# SCH_Iris_OnBoardSystem_Schematic.net
KiCad netlist of a schematic drawn in EasyEDA
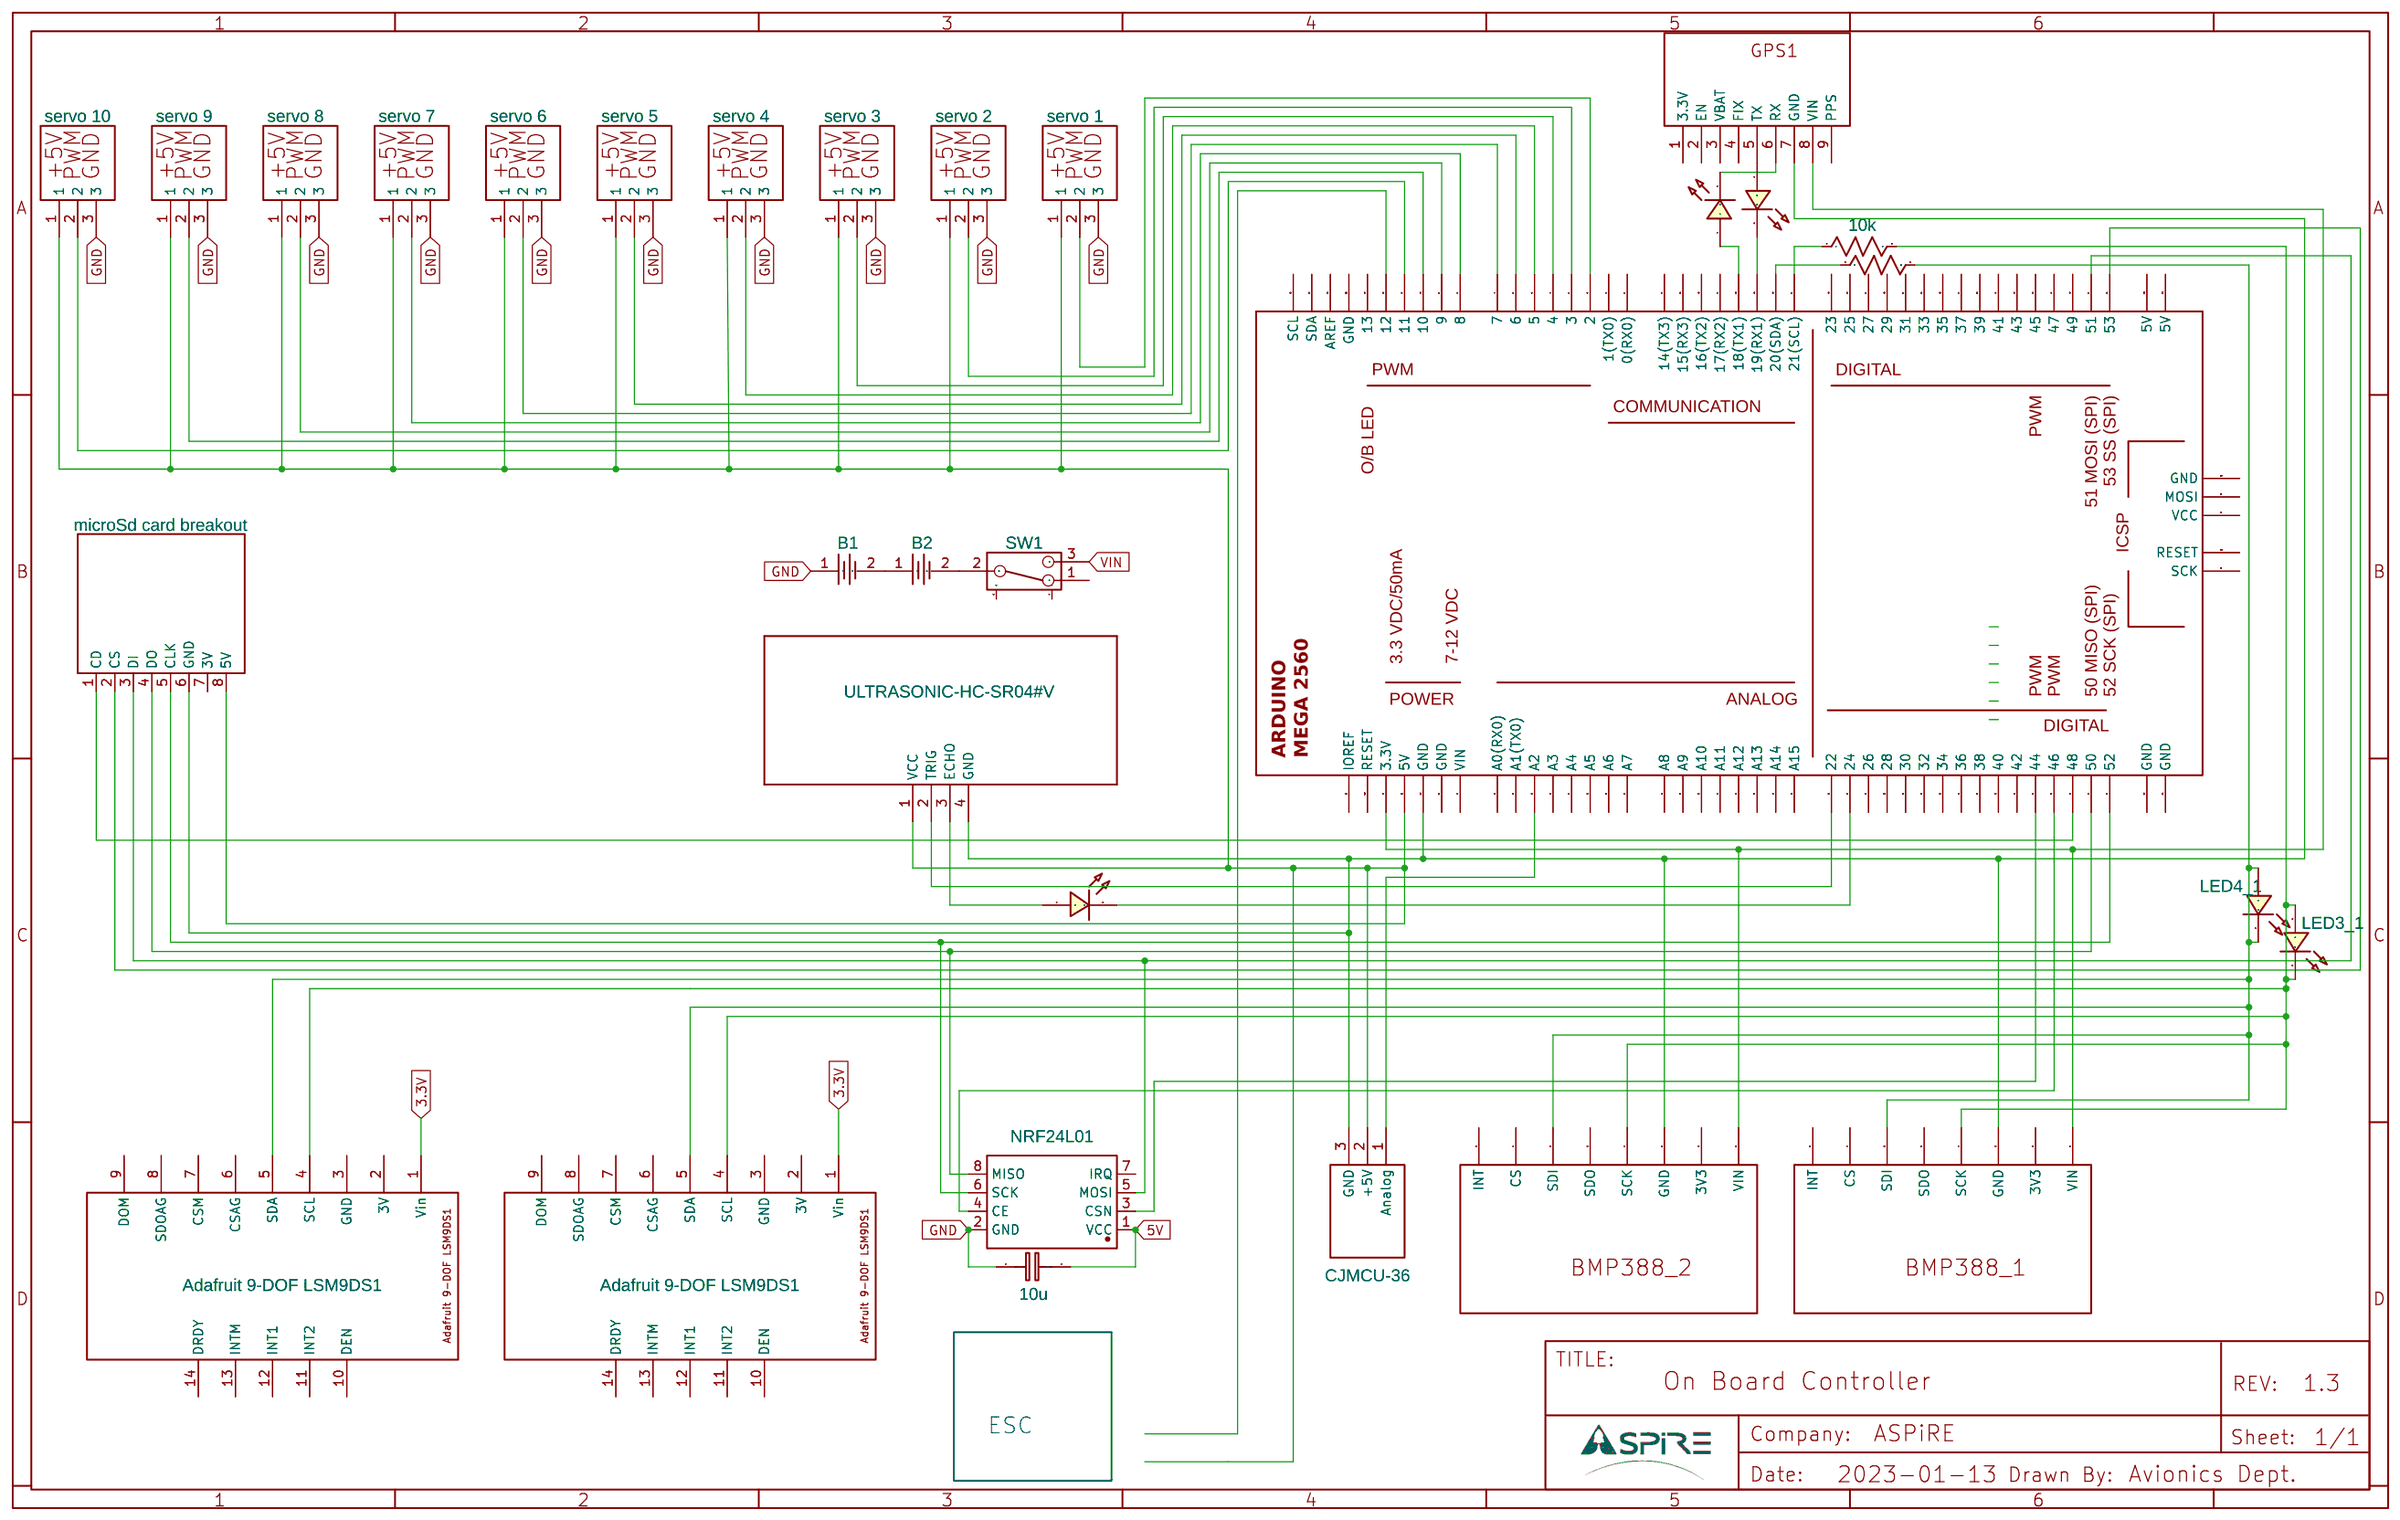
[diagram p0: schematic sheet]

(export (version "E")
  (design (tool "Eeschema 10.0.6"))
  (components
    (comp (ref "B1")
      (value "CR1220-2")
      (fields (field (name "BOM_Supplier Part") "C70381"))
      (libsource (lib "") (part "CR1220-2"))
    )
    (comp (ref "B2")
      (value "CR1220-2")
      (fields (field (name "BOM_Supplier Part") "C70381"))
      (libsource (lib "") (part "CR1220-2"))
    )
    (comp (ref "C1_1") (value "10u") (libsource (lib "") (part "C_RAD-0.1_EU")))
    (comp (ref "CD") (value "microSd card breakout") (libsource (lib "") (part "microSd card breakout")))
    (comp (ref "GPS1")
      (value "ULTIMATE GPS MODULE")
      (fields
        (field (name "BOM_Manufacturer Part") "Solid State Relays")
        (field (name "BOM_Supplier Part") "746")
      )
      (libsource (lib "") (part "ULTIMATE GPS MODULE"))
    )
    (comp (ref "LED1_1")
      (value "LED-TH-3mm_R")
      (fields
        (field (name "BOM_Manufacturer Part") "204-10SDRD/S530-A3-L")
        (field (name "BOM_Supplier Part") "C84774")
      )
      (libsource (lib "") (part "LED-TH-3mm_R_4"))
    )
    (comp (ref "LED2_1")
      (value "LED-TH-3mm_R")
      (fields
        (field (name "BOM_Manufacturer Part") "204-10SDRD/S530-A3-L")
        (field (name "BOM_Supplier Part") "C84774")
      )
      (libsource (lib "") (part "LED-TH-3mm_R_1"))
    )
    (comp (ref "LED3_1")
      (value "LED-TH-3mm_R")
      (fields
        (field (name "BOM_Manufacturer Part") "204-10SDRD/S530-A3-L")
        (field (name "BOM_Supplier Part") "C84774")
      )
      (libsource (lib "") (part "LED-TH-3mm_R_2"))
    )
    (comp (ref "LED4_1")
      (value "LED-TH-3mm_R")
      (fields
        (field (name "BOM_Manufacturer Part") "204-10SDRD/S530-A3-L")
        (field (name "BOM_Supplier Part") "C84774")
      )
      (libsource (lib "") (part "LED-TH-3mm_R"))
    )
    (comp (ref "LED5_1")
      (value "LED-TH-3mm_R")
      (fields
        (field (name "BOM_Manufacturer Part") "204-10SDRD/S530-A3-L")
        (field (name "BOM_Supplier Part") "C84774")
      )
      (libsource (lib "") (part "LED-TH-3mm_R_3"))
    )
    (comp (ref "MK1")
      (value "NRF24L01")
      (fields (field (name "BOM_Manufacturer Part") "NF-04") (field (name "BOM_Supplier Part") "C90751"))
      (libsource (lib "") (part "NRF24L01"))
    )
    (comp (ref "R1_1") (value "1k") (libsource (lib "") (part "R_AXIAL-0.4_US_1")))
    (comp (ref "R2_1") (value "10k") (libsource (lib "") (part "R_AXIAL-0.4_US")))
    (comp (ref "SW1")
      (value "SK-12D02-VG5")
      (fields (field (name "BOM_Supplier Part") "C136722"))
      (libsource (lib "") (part "SK-12D02-VG5"))
    )
    (comp (ref "U1")
      (value "Adafruit 9-DOF LSM9DS1")
      (fields (field (name "BOM_Manufacturer Part") "4634") (field (name "BOM_Supplier Part") "ADA4634"))
      (libsource (lib "") (part "Adafruit 9-DOF LSM9DS1"))
    )
    (comp (ref "U4")
      (value "ADAFRUIT_BMP388_1")
      (fields (field (name "BOM_Manufacturer Part") "BMP388") (field (name "BOM_Supplier Part") "3966"))
      (libsource (lib "") (part "ADAFRUIT BMP388 BOARD COPY_1"))
    )
    (comp (ref "U5")
      (value "ADAFRUIT_BMP388_2")
      (fields (field (name "BOM_Manufacturer Part") "BMP388") (field (name "BOM_Supplier Part") "3966"))
      (libsource (lib "") (part "ADAFRUIT BMP388 BOARD COPY"))
    )
    (comp (ref "U6") (value "Am") (libsource (lib "") (part "Am")))
    (comp (ref "U15")
      (value "Adafruit 9-DOF LSM9DS1")
      (fields (field (name "BOM_Manufacturer Part") "4634") (field (name "BOM_Supplier Part") "ADA4634"))
      (libsource (lib "") (part "Adafruit 9-DOF LSM9DS1"))
    )
    (comp (ref "U16") (value "CJMCU-36") (libsource (lib "") (part "CJMCU-36")))
    (comp (ref "U17") (value "ULTRASONIC-HC-SR04#V") (libsource (lib "") (part "ULTRASONIC-HC-SR04#V")))
    (comp (ref "U18") (value "servo 10") (libsource (lib "") (part "servo")))
    (comp (ref "U19") (value "servo 9") (libsource (lib "") (part "servo")))
    (comp (ref "U20") (value "servo 8") (libsource (lib "") (part "servo")))
    (comp (ref "U21") (value "servo 7") (libsource (lib "") (part "servo")))
    (comp (ref "U22") (value "servo 6") (libsource (lib "") (part "servo")))
    (comp (ref "U23") (value "servo 5") (libsource (lib "") (part "servo")))
    (comp (ref "U24") (value "servo 4") (libsource (lib "") (part "servo")))
    (comp (ref "U25") (value "servo 3") (libsource (lib "") (part "servo")))
    (comp (ref "U26") (value "servo 2") (libsource (lib "") (part "servo")))
    (comp (ref "U27") (value "servo 1") (libsource (lib "") (part "servo")))
  )
  (nets
    (net (code "1") (name "3.3V") (class "Default")
      (node (ref "U1") (pin "1") (pinfunction "Vin_1") (pintype "unspecified"))
      (node (ref "U15") (pin "1") (pinfunction "Vin_1") (pintype "unspecified"))
    )
    (net (code "2") (name "5V") (class "Default")
      (node (ref "C1_1") (pin "2") (pinfunction "2_2") (pintype "unspecified"))
      (node (ref "MK1") (pin "1") (pinfunction "VCC_1") (pintype "unspecified"))
    )
    (net (code "3") (name "GND") (class "Default")
      (node (ref "B1") (pin "1") (pinfunction "1_1") (pintype "input"))
      (node (ref "C1_1") (pin "1") (pinfunction "1_1") (pintype "unspecified"))
      (node (ref "MK1") (pin "2") (pinfunction "GND_2") (pintype "unspecified"))
      (node (ref "U18") (pin "3") (pinfunction "3_3") (pintype "unspecified"))
      (node (ref "U19") (pin "3") (pinfunction "3_3") (pintype "unspecified"))
      (node (ref "U20") (pin "3") (pinfunction "3_3") (pintype "unspecified"))
      (node (ref "U21") (pin "3") (pinfunction "3_3") (pintype "unspecified"))
      (node (ref "U22") (pin "3") (pinfunction "3_3") (pintype "unspecified"))
      (node (ref "U23") (pin "3") (pinfunction "3_3") (pintype "unspecified"))
      (node (ref "U24") (pin "3") (pinfunction "3_3") (pintype "unspecified"))
      (node (ref "U25") (pin "3") (pinfunction "3_3") (pintype "unspecified"))
      (node (ref "U26") (pin "3") (pinfunction "3_3") (pintype "unspecified"))
      (node (ref "U27") (pin "3") (pinfunction "3_3") (pintype "unspecified"))
    )
    (net (code "4") (name "Net-(B1-Pad2)") (class "Default")
      (node (ref "B1") (pin "2") (pinfunction "2_2") (pintype "input"))
      (node (ref "B2") (pin "1") (pinfunction "1_1") (pintype "input"))
    )
    (net (code "5") (name "Net-(B2-Pad2)") (class "Default")
      (node (ref "B2") (pin "2") (pinfunction "2_2") (pintype "input"))
      (node (ref "SW1") (pin "2") (pinfunction "2_2") (pintype "unspecified"))
    )
    (net (code "6") (name "Net-(CD-5V)") (class "Default")
      (node (ref "CD") (pin "8") (pinfunction "5V_8") (pintype "passive"))
      (node (ref "U16") (pin "2") (pinfunction "+5V_2") (pintype "unspecified"))
      (node (ref "U17") (pin "1") (pinfunction "VCC_1") (pintype "passive"))
      (node (ref "U18") (pin "1") (pinfunction "1_1") (pintype "unspecified"))
      (node (ref "U19") (pin "1") (pinfunction "1_1") (pintype "unspecified"))
      (node (ref "U20") (pin "1") (pinfunction "1_1") (pintype "unspecified"))
      (node (ref "U21") (pin "1") (pinfunction "1_1") (pintype "unspecified"))
      (node (ref "U22") (pin "1") (pinfunction "1_1") (pintype "unspecified"))
      (node (ref "U23") (pin "1") (pinfunction "1_1") (pintype "unspecified"))
      (node (ref "U24") (pin "1") (pinfunction "1_1") (pintype "unspecified"))
      (node (ref "U25") (pin "1") (pinfunction "1_1") (pintype "unspecified"))
      (node (ref "U26") (pin "1") (pinfunction "1_1") (pintype "unspecified"))
      (node (ref "U27") (pin "1") (pinfunction "1_1") (pintype "unspecified"))
      (node (ref "U6") (pin "5V@0") (pinfunction "5V_5V@0") (pintype "unspecified"))
    )
    (net (code "7") (name "Net-(CD-CD)") (class "Default")
      (node (ref "CD") (pin "1") (pinfunction "CD_1") (pintype "unspecified"))
      (node (ref "U6") (pin "48") (pinfunction "48_48") (pintype "unspecified"))
    )
    (net (code "8") (name "Net-(CD-CLK)") (class "Default")
      (node (ref "CD") (pin "5") (pinfunction "CLK_5") (pintype "input"))
      (node (ref "MK1") (pin "6") (pinfunction "SCK_6") (pintype "unspecified"))
      (node (ref "U6") (pin "52") (pinfunction "52_52") (pintype "unspecified"))
    )
    (net (code "9") (name "Net-(CD-CS)") (class "Default")
      (node (ref "CD") (pin "2") (pinfunction "CS_2") (pintype "input"))
      (node (ref "U6") (pin "53") (pinfunction "53_53") (pintype "unspecified"))
    )
    (net (code "10") (name "Net-(CD-DI)") (class "Default")
      (node (ref "CD") (pin "3") (pinfunction "DI_3") (pintype "bidirectional"))
      (node (ref "MK1") (pin "5") (pinfunction "MOSI_5") (pintype "unspecified"))
      (node (ref "U6") (pin "51") (pinfunction "51_51") (pintype "unspecified"))
    )
    (net (code "11") (name "Net-(CD-DO)") (class "Default")
      (node (ref "CD") (pin "4") (pinfunction "DO_4") (pintype "bidirectional"))
      (node (ref "MK1") (pin "8") (pinfunction "MISO_8") (pintype "unspecified"))
      (node (ref "U6") (pin "50") (pinfunction "50_50") (pintype "unspecified"))
    )
    (net (code "12") (name "Net-(CD-GND)") (class "Default")
      (node (ref "CD") (pin "6") (pinfunction "GND_6") (pintype "passive"))
      (node (ref "GPS1") (pin "7") (pinfunction "GND_7") (pintype "unspecified"))
      (node (ref "U16") (pin "3") (pinfunction "GND_3") (pintype "unspecified"))
      (node (ref "U17") (pin "4") (pinfunction "GND_4") (pintype "passive"))
      (node (ref "U4") (pin "3") (pinfunction "GND_3") (pintype "passive"))
      (node (ref "U5") (pin "3") (pinfunction "GND_3") (pintype "passive"))
      (node (ref "U6") (pin "GND@0") (pinfunction "GND_GND@0") (pintype "unspecified"))
    )
    (net (code "13") (name "Net-(GPS1-RX)") (class "Default")
      (node (ref "GPS1") (pin "6") (pinfunction "RX_6") (pintype "unspecified"))
      (node (ref "LED5_1") (pin "2") (pinfunction "2_2") (pintype "unspecified"))
    )
    (net (code "14") (name "Net-(GPS1-TX)") (class "Default")
      (node (ref "GPS1") (pin "5") (pinfunction "TX_5") (pintype "unspecified"))
      (node (ref "LED2_1") (pin "1") (pinfunction "1_1") (pintype "unspecified"))
    )
    (net (code "15") (name "Net-(GPS1-VIN)") (class "Default")
      (node (ref "GPS1") (pin "8") (pinfunction "VIN_8") (pintype "unspecified"))
      (node (ref "U4") (pin "1") (pinfunction "VIN_1") (pintype "passive"))
      (node (ref "U5") (pin "1") (pinfunction "VIN_1") (pintype "passive"))
      (node (ref "U6") (pin "3.3V") (pinfunction "3.3V_3.3V") (pintype "unspecified"))
    )
    (net (code "16") (name "Net-(LED1_1-Pad2)") (class "Default")
      (node (ref "LED1_1") (pin "2") (pinfunction "2_2") (pintype "unspecified"))
      (node (ref "U6") (pin "24") (pinfunction "24_24") (pintype "unspecified"))
    )
    (net (code "17") (name "Net-(MK1-CE)") (class "Default")
      (node (ref "MK1") (pin "4") (pinfunction "CE_4") (pintype "unspecified"))
      (node (ref "U6") (pin "46") (pinfunction "46_46") (pintype "unspecified"))
    )
    (net (code "18") (name "Net-(MK1-CSN)") (class "Default")
      (node (ref "MK1") (pin "3") (pinfunction "CSN_3") (pintype "unspecified"))
      (node (ref "U6") (pin "44") (pinfunction "44_44") (pintype "unspecified"))
    )
    (net (code "19") (name "Net-(U1-SCL)") (class "Default")
      (node (ref "LED3_1") (pin "1") (pinfunction "1_1") (pintype "unspecified"))
      (node (ref "LED3_1") (pin "2") (pinfunction "2_2") (pintype "unspecified"))
      (node (ref "R2_1") (pin "2") (pinfunction "2_2") (pintype "unspecified"))
      (node (ref "U1") (pin "4") (pinfunction "SCL_4") (pintype "unspecified"))
      (node (ref "U15") (pin "4") (pinfunction "SCL_4") (pintype "unspecified"))
      (node (ref "U4") (pin "4") (pinfunction "SCK_4") (pintype "input"))
      (node (ref "U5") (pin "4") (pinfunction "SCK_4") (pintype "input"))
    )
    (net (code "20") (name "Net-(U1-SDA)") (class "Default")
      (node (ref "LED4_1") (pin "1") (pinfunction "1_1") (pintype "unspecified"))
      (node (ref "LED4_1") (pin "2") (pinfunction "2_2") (pintype "unspecified"))
      (node (ref "R1_1") (pin "2") (pinfunction "2_2") (pintype "unspecified"))
      (node (ref "U1") (pin "5") (pinfunction "SDA_5") (pintype "unspecified"))
      (node (ref "U15") (pin "5") (pinfunction "SDA_5") (pintype "unspecified"))
      (node (ref "U4") (pin "6") (pinfunction "SDI_6") (pintype "bidirectional"))
      (node (ref "U5") (pin "6") (pinfunction "SDI_6") (pintype "bidirectional"))
    )
    (net (code "21") (name "Net-(U6-18(TX1))") (class "Default")
      (node (ref "LED5_1") (pin "1") (pinfunction "1_1") (pintype "unspecified"))
      (node (ref "U6") (pin "18") (pinfunction "18(TX1)_18") (pintype "unspecified"))
    )
    (net (code "22") (name "Net-(U6-19(RX1))") (class "Default")
      (node (ref "LED2_1") (pin "2") (pinfunction "2_2") (pintype "unspecified"))
      (node (ref "U6") (pin "19") (pinfunction "19(RX1)_19") (pintype "unspecified"))
    )
    (net (code "23") (name "Net-(U6-20(SDA))") (class "Default")
      (node (ref "R1_1") (pin "1") (pinfunction "1_1") (pintype "unspecified"))
      (node (ref "U6") (pin "20") (pinfunction "20(SDA)_20") (pintype "unspecified"))
    )
    (net (code "24") (name "Net-(U6-21(SCL))") (class "Default")
      (node (ref "R2_1") (pin "1") (pinfunction "1_1") (pintype "unspecified"))
      (node (ref "U6") (pin "21") (pinfunction "21(SCL)_21") (pintype "unspecified"))
    )
    (net (code "25") (name "Net-(U16-Analog)") (class "Default")
      (node (ref "U16") (pin "1") (pinfunction "Analog_1") (pintype "unspecified"))
      (node (ref "U6") (pin "A2") (pinfunction "A2_A2") (pintype "unspecified"))
    )
    (net (code "26") (name "Net-(U17-ECHO)") (class "Default")
      (node (ref "LED1_1") (pin "1") (pinfunction "1_1") (pintype "unspecified"))
      (node (ref "U17") (pin "3") (pinfunction "ECHO_3") (pintype "output"))
    )
    (net (code "27") (name "Net-(U17-TRIG)") (class "Default")
      (node (ref "U17") (pin "2") (pinfunction "TRIG_2") (pintype "input"))
      (node (ref "U6") (pin "22") (pinfunction "22_22") (pintype "unspecified"))
    )
    (net (code "28") (name "Net-(U18-Pad2)") (class "Default")
      (node (ref "U18") (pin "2") (pinfunction "2_2") (pintype "unspecified"))
      (node (ref "U6") (pin "11") (pinfunction "11_11") (pintype "unspecified"))
    )
    (net (code "29") (name "Net-(U19-Pad2)") (class "Default")
      (node (ref "U19") (pin "2") (pinfunction "2_2") (pintype "unspecified"))
      (node (ref "U6") (pin "10") (pinfunction "10_10") (pintype "unspecified"))
    )
    (net (code "30") (name "Net-(U20-Pad2)") (class "Default")
      (node (ref "U20") (pin "2") (pinfunction "2_2") (pintype "unspecified"))
      (node (ref "U6") (pin "9") (pinfunction "9_9") (pintype "unspecified"))
    )
    (net (code "31") (name "Net-(U21-Pad2)") (class "Default")
      (node (ref "U21") (pin "2") (pinfunction "2_2") (pintype "unspecified"))
      (node (ref "U6") (pin "8") (pinfunction "8_8") (pintype "unspecified"))
    )
    (net (code "32") (name "Net-(U22-Pad2)") (class "Default")
      (node (ref "U22") (pin "2") (pinfunction "2_2") (pintype "unspecified"))
      (node (ref "U6") (pin "7") (pinfunction "7_7") (pintype "unspecified"))
    )
    (net (code "33") (name "Net-(U23-Pad2)") (class "Default")
      (node (ref "U23") (pin "2") (pinfunction "2_2") (pintype "unspecified"))
      (node (ref "U6") (pin "6") (pinfunction "6_6") (pintype "unspecified"))
    )
    (net (code "34") (name "Net-(U24-Pad2)") (class "Default")
      (node (ref "U24") (pin "2") (pinfunction "2_2") (pintype "unspecified"))
      (node (ref "U6") (pin "5") (pinfunction "5_5") (pintype "unspecified"))
    )
    (net (code "35") (name "Net-(U25-Pad2)") (class "Default")
      (node (ref "U25") (pin "2") (pinfunction "2_2") (pintype "unspecified"))
      (node (ref "U6") (pin "4") (pinfunction "4_4") (pintype "unspecified"))
    )
    (net (code "36") (name "Net-(U26-Pad2)") (class "Default")
      (node (ref "U26") (pin "2") (pinfunction "2_2") (pintype "unspecified"))
      (node (ref "U6") (pin "3") (pinfunction "3_3") (pintype "unspecified"))
    )
    (net (code "37") (name "Net-(U27-Pad2)") (class "Default")
      (node (ref "U27") (pin "2") (pinfunction "2_2") (pintype "unspecified"))
      (node (ref "U6") (pin "2") (pinfunction "2_2") (pintype "unspecified"))
    )
    (net (code "38") (name "VIN") (class "Default")
      (node (ref "SW1") (pin "3") (pinfunction "3_3") (pintype "unspecified"))
    )
    (net (code "39") (name "unconnected-(CD-3V-Pad7)") (class "Default")
      (node (ref "CD") (pin "7") (pinfunction "3V_7") (pintype "passive"))
    )
    (net (code "40") (name "unconnected-(GPS1-3.3V-Pad1)") (class "Default")
      (node (ref "GPS1") (pin "1") (pinfunction "3.3V_1") (pintype "unspecified"))
    )
    (net (code "41") (name "unconnected-(GPS1-EN-Pad2)") (class "Default")
      (node (ref "GPS1") (pin "2") (pinfunction "EN_2") (pintype "unspecified"))
    )
    (net (code "42") (name "unconnected-(GPS1-FIX-Pad4)") (class "Default")
      (node (ref "GPS1") (pin "4") (pinfunction "FIX_4") (pintype "unspecified"))
    )
    (net (code "43") (name "unconnected-(GPS1-PPS-Pad9)") (class "Default")
      (node (ref "GPS1") (pin "9") (pinfunction "PPS_9") (pintype "unspecified"))
    )
    (net (code "44") (name "unconnected-(GPS1-VBAT-Pad3)") (class "Default")
      (node (ref "GPS1") (pin "3") (pinfunction "VBAT_3") (pintype "unspecified"))
    )
    (net (code "45") (name "unconnected-(MK1-IRQ-Pad7)") (class "Default")
      (node (ref "MK1") (pin "7") (pinfunction "IRQ_7") (pintype "unspecified"))
    )
    (net (code "46") (name "unconnected-(SW1-Pad1)") (class "Default")
      (node (ref "SW1") (pin "1") (pinfunction "1_1") (pintype "unspecified"))
    )
    (net (code "47") (name "unconnected-(SW1-Pad4)") (class "Default")
      (node (ref "SW1") (pin "4") (pinfunction "4_4") (pintype "unspecified"))
    )
    (net (code "48") (name "unconnected-(SW1-Pad5)") (class "Default")
      (node (ref "SW1") (pin "5") (pinfunction "5_5") (pintype "unspecified"))
    )
    (net (code "49") (name "unconnected-(U1-3V-Pad2)") (class "Default")
      (node (ref "U1") (pin "2") (pinfunction "3V_2") (pintype "unspecified"))
    )
    (net (code "50") (name "unconnected-(U1-CSAG-Pad6)") (class "Default")
      (node (ref "U1") (pin "6") (pinfunction "CSAG_6") (pintype "unspecified"))
    )
    (net (code "51") (name "unconnected-(U1-CSM-Pad7)") (class "Default")
      (node (ref "U1") (pin "7") (pinfunction "CSM_7") (pintype "unspecified"))
    )
    (net (code "52") (name "unconnected-(U1-DEN-Pad10)") (class "Default")
      (node (ref "U1") (pin "10") (pinfunction "DEN_10") (pintype "unspecified"))
    )
    (net (code "53") (name "unconnected-(U1-DOM-Pad9)") (class "Default")
      (node (ref "U1") (pin "9") (pinfunction "DOM_9") (pintype "unspecified"))
    )
    (net (code "54") (name "unconnected-(U1-DRDY-Pad14)") (class "Default")
      (node (ref "U1") (pin "14") (pinfunction "DRDY_14") (pintype "unspecified"))
    )
    (net (code "55") (name "unconnected-(U1-GND-Pad3)") (class "Default")
      (node (ref "U1") (pin "3") (pinfunction "GND_3") (pintype "unspecified"))
    )
    (net (code "56") (name "unconnected-(U1-INT1-Pad12)") (class "Default")
      (node (ref "U1") (pin "12") (pinfunction "INT1_12") (pintype "unspecified"))
    )
    (net (code "57") (name "unconnected-(U1-INT2-Pad11)") (class "Default")
      (node (ref "U1") (pin "11") (pinfunction "INT2_11") (pintype "unspecified"))
    )
    (net (code "58") (name "unconnected-(U1-INTM-Pad13)") (class "Default")
      (node (ref "U1") (pin "13") (pinfunction "INTM_13") (pintype "unspecified"))
    )
    (net (code "59") (name "unconnected-(U1-SDOAG-Pad8)") (class "Default")
      (node (ref "U1") (pin "8") (pinfunction "SDOAG_8") (pintype "unspecified"))
    )
    (net (code "60") (name "unconnected-(U4-3V3-Pad2)") (class "Default")
      (node (ref "U4") (pin "2") (pinfunction "3V3_2") (pintype "passive"))
    )
    (net (code "61") (name "unconnected-(U4-CS-Pad7)") (class "Default")
      (node (ref "U4") (pin "7") (pinfunction "CS_7") (pintype "bidirectional"))
    )
    (net (code "62") (name "unconnected-(U4-INT-Pad8)") (class "Default")
      (node (ref "U4") (pin "8") (pinfunction "INT_8") (pintype "bidirectional"))
    )
    (net (code "63") (name "unconnected-(U4-SDO-Pad5)") (class "Default")
      (node (ref "U4") (pin "5") (pinfunction "SDO_5") (pintype "bidirectional"))
    )
    (net (code "64") (name "unconnected-(U5-3V3-Pad2)") (class "Default")
      (node (ref "U5") (pin "2") (pinfunction "3V3_2") (pintype "passive"))
    )
    (net (code "65") (name "unconnected-(U5-CS-Pad7)") (class "Default")
      (node (ref "U5") (pin "7") (pinfunction "CS_7") (pintype "bidirectional"))
    )
    (net (code "66") (name "unconnected-(U5-INT-Pad8)") (class "Default")
      (node (ref "U5") (pin "8") (pinfunction "INT_8") (pintype "bidirectional"))
    )
    (net (code "67") (name "unconnected-(U5-SDO-Pad5)") (class "Default")
      (node (ref "U5") (pin "5") (pinfunction "SDO_5") (pintype "bidirectional"))
    )
    (net (code "68") (name "unconnected-(U6-0(RX0)-Pad0)") (class "Default")
      (node (ref "U6") (pin "0") (pinfunction "0(RX0)_0") (pintype "unspecified"))
    )
    (net (code "69") (name "unconnected-(U6-1(TX0)-Pad1)") (class "Default")
      (node (ref "U6") (pin "1") (pinfunction "1(TX0)_1") (pintype "unspecified"))
    )
    (net (code "70") (name "unconnected-(U6-5V-Pad5V@1)") (class "Default")
      (node (ref "U6") (pin "5V@1") (pinfunction "5V_5V@1") (pintype "unspecified"))
    )
    (net (code "71") (name "unconnected-(U6-5V-Pad5V@2)") (class "Default")
      (node (ref "U6") (pin "5V@2") (pinfunction "5V_5V@2") (pintype "unspecified"))
    )
    (net (code "72") (name "unconnected-(U6-14(TX3)-Pad14)") (class "Default")
      (node (ref "U6") (pin "14") (pinfunction "14(TX3)_14") (pintype "unspecified"))
    )
    (net (code "73") (name "unconnected-(U6-15(RX3)-Pad15)") (class "Default")
      (node (ref "U6") (pin "15") (pinfunction "15(RX3)_15") (pintype "unspecified"))
    )
    (net (code "74") (name "unconnected-(U6-16(TX2)-Pad16)") (class "Default")
      (node (ref "U6") (pin "16") (pinfunction "16(TX2)_16") (pintype "unspecified"))
    )
    (net (code "75") (name "unconnected-(U6-17(RX2)-Pad17)") (class "Default")
      (node (ref "U6") (pin "17") (pinfunction "17(RX2)_17") (pintype "unspecified"))
    )
    (net (code "76") (name "unconnected-(U6-A0(RX0)-PadA0)") (class "Default")
      (node (ref "U6") (pin "A0") (pinfunction "A0(RX0)_A0") (pintype "unspecified"))
    )
    (net (code "77") (name "unconnected-(U6-A1(TX0)-PadA1)") (class "Default")
      (node (ref "U6") (pin "A1") (pinfunction "A1(TX0)_A1") (pintype "unspecified"))
    )
    (net (code "78") (name "unconnected-(U6-GND-PadGND@1)") (class "Default")
      (node (ref "U6") (pin "GND@1") (pinfunction "GND_GND@1") (pintype "unspecified"))
    )
    (net (code "79") (name "unconnected-(U6-GND-PadGND@2)") (class "Default")
      (node (ref "U6") (pin "GND@2") (pinfunction "GND_GND@2") (pintype "unspecified"))
    )
    (net (code "80") (name "unconnected-(U6-GND-PadGND@3)") (class "Default")
      (node (ref "U6") (pin "GND@3") (pinfunction "GND_GND@3") (pintype "unspecified"))
    )
    (net (code "81") (name "unconnected-(U6-GND-PadGND@4)") (class "Default")
      (node (ref "U6") (pin "GND@4") (pinfunction "GND_GND@4") (pintype "unspecified"))
    )
    (net (code "82") (name "unconnected-(U6-GND-PadGND@5)") (class "Default")
      (node (ref "U6") (pin "GND@5") (pinfunction "GND_GND@5") (pintype "unspecified"))
    )
    (net (code "83") (name "unconnected-(U6-Pad12)") (class "Default")
      (node (ref "U6") (pin "12") (pinfunction "12_12") (pintype "unspecified"))
    )
    (net (code "84") (name "unconnected-(U6-Pad13)") (class "Default")
      (node (ref "U6") (pin "13") (pinfunction "13_13") (pintype "unspecified"))
    )
    (net (code "85") (name "unconnected-(U6-Pad23)") (class "Default")
      (node (ref "U6") (pin "23") (pinfunction "23_23") (pintype "unspecified"))
    )
    (net (code "86") (name "unconnected-(U6-Pad25)") (class "Default")
      (node (ref "U6") (pin "25") (pinfunction "25_25") (pintype "unspecified"))
    )
    (net (code "87") (name "unconnected-(U6-Pad26)") (class "Default")
      (node (ref "U6") (pin "26") (pinfunction "26_26") (pintype "unspecified"))
    )
    (net (code "88") (name "unconnected-(U6-Pad27)") (class "Default")
      (node (ref "U6") (pin "27") (pinfunction "27_27") (pintype "unspecified"))
    )
    (net (code "89") (name "unconnected-(U6-Pad28)") (class "Default")
      (node (ref "U6") (pin "28") (pinfunction "28_28") (pintype "unspecified"))
    )
    (net (code "90") (name "unconnected-(U6-Pad29)") (class "Default")
      (node (ref "U6") (pin "29") (pinfunction "29_29") (pintype "unspecified"))
    )
    (net (code "91") (name "unconnected-(U6-Pad30)") (class "Default")
      (node (ref "U6") (pin "30") (pinfunction "30_30") (pintype "unspecified"))
    )
    (net (code "92") (name "unconnected-(U6-Pad31)") (class "Default")
      (node (ref "U6") (pin "31") (pinfunction "31_31") (pintype "unspecified"))
    )
    (net (code "93") (name "unconnected-(U6-Pad32)") (class "Default")
      (node (ref "U6") (pin "32") (pinfunction "32_32") (pintype "unspecified"))
    )
    (net (code "94") (name "unconnected-(U6-Pad33)") (class "Default")
      (node (ref "U6") (pin "33") (pinfunction "33_33") (pintype "unspecified"))
    )
    (net (code "95") (name "unconnected-(U6-Pad34)") (class "Default")
      (node (ref "U6") (pin "34") (pinfunction "34_34") (pintype "unspecified"))
    )
    (net (code "96") (name "unconnected-(U6-Pad35)") (class "Default")
      (node (ref "U6") (pin "35") (pinfunction "35_35") (pintype "unspecified"))
    )
    (net (code "97") (name "unconnected-(U6-Pad36)") (class "Default")
      (node (ref "U6") (pin "36") (pinfunction "36_36") (pintype "unspecified"))
    )
    (net (code "98") (name "unconnected-(U6-Pad37)") (class "Default")
      (node (ref "U6") (pin "37") (pinfunction "37_37") (pintype "unspecified"))
    )
    (net (code "99") (name "unconnected-(U6-Pad38)") (class "Default")
      (node (ref "U6") (pin "38") (pinfunction "38_38") (pintype "unspecified"))
    )
    (net (code "100") (name "unconnected-(U6-Pad39)") (class "Default")
      (node (ref "U6") (pin "39") (pinfunction "39_39") (pintype "unspecified"))
    )
    (net (code "101") (name "unconnected-(U6-Pad40)") (class "Default")
      (node (ref "U6") (pin "40") (pinfunction "40_40") (pintype "unspecified"))
    )
    (net (code "102") (name "unconnected-(U6-Pad41)") (class "Default")
      (node (ref "U6") (pin "41") (pinfunction "41_41") (pintype "unspecified"))
    )
    (net (code "103") (name "unconnected-(U6-Pad42)") (class "Default")
      (node (ref "U6") (pin "42") (pinfunction "42_42") (pintype "unspecified"))
    )
    (net (code "104") (name "unconnected-(U6-Pad43)") (class "Default")
      (node (ref "U6") (pin "43") (pinfunction "43_43") (pintype "unspecified"))
    )
    (net (code "105") (name "unconnected-(U6-Pad45)") (class "Default")
      (node (ref "U6") (pin "45") (pinfunction "45_45") (pintype "unspecified"))
    )
    (net (code "106") (name "unconnected-(U6-Pad47)") (class "Default")
      (node (ref "U6") (pin "47") (pinfunction "47_47") (pintype "unspecified"))
    )
    (net (code "107") (name "unconnected-(U6-Pad49)") (class "Default")
      (node (ref "U6") (pin "49") (pinfunction "49_49") (pintype "unspecified"))
    )
    (net (code "108") (name "unconnected-(U6-PadA3)") (class "Default")
      (node (ref "U6") (pin "A3") (pinfunction "A3_A3") (pintype "unspecified"))
    )
    (net (code "109") (name "unconnected-(U6-PadA4)") (class "Default")
      (node (ref "U6") (pin "A4") (pinfunction "A4_A4") (pintype "unspecified"))
    )
    (net (code "110") (name "unconnected-(U6-PadA5)") (class "Default")
      (node (ref "U6") (pin "A5") (pinfunction "A5_A5") (pintype "unspecified"))
    )
    (net (code "111") (name "unconnected-(U6-PadA6)") (class "Default")
      (node (ref "U6") (pin "A6") (pinfunction "A6_A6") (pintype "unspecified"))
    )
    (net (code "112") (name "unconnected-(U6-PadA7)") (class "Default")
      (node (ref "U6") (pin "A7") (pinfunction "A7_A7") (pintype "unspecified"))
    )
    (net (code "113") (name "unconnected-(U6-PadA8)") (class "Default")
      (node (ref "U6") (pin "A8") (pinfunction "A8_A8") (pintype "unspecified"))
    )
    (net (code "114") (name "unconnected-(U6-PadA9)") (class "Default")
      (node (ref "U6") (pin "A9") (pinfunction "A9_A9") (pintype "unspecified"))
    )
    (net (code "115") (name "unconnected-(U6-PadA10)") (class "Default")
      (node (ref "U6") (pin "A10") (pinfunction "A10_A10") (pintype "unspecified"))
    )
    (net (code "116") (name "unconnected-(U6-PadA11)") (class "Default")
      (node (ref "U6") (pin "A11") (pinfunction "A11_A11") (pintype "unspecified"))
    )
    (net (code "117") (name "unconnected-(U6-PadA12)") (class "Default")
      (node (ref "U6") (pin "A12") (pinfunction "A12_A12") (pintype "unspecified"))
    )
    (net (code "118") (name "unconnected-(U6-PadA13)") (class "Default")
      (node (ref "U6") (pin "A13") (pinfunction "A13_A13") (pintype "unspecified"))
    )
    (net (code "119") (name "unconnected-(U6-PadA14)") (class "Default")
      (node (ref "U6") (pin "A14") (pinfunction "A14_A14") (pintype "unspecified"))
    )
    (net (code "120") (name "unconnected-(U6-PadA15)") (class "Default")
      (node (ref "U6") (pin "A15") (pinfunction "A15_A15") (pintype "unspecified"))
    )
    (net (code "121") (name "unconnected-(U6-PadAREF)") (class "Default")
      (node (ref "U6") (pin "AREF") (pinfunction "AREF_AREF") (pintype "unspecified"))
    )
    (net (code "122") (name "unconnected-(U6-PadIOREF)") (class "Default")
      (node (ref "U6") (pin "IOREF") (pinfunction "IOREF_IOREF") (pintype "unspecified"))
    )
    (net (code "123") (name "unconnected-(U6-PadMOSI)") (class "Default")
      (node (ref "U6") (pin "MOSI") (pinfunction "MOSI_MOSI") (pintype "unspecified"))
    )
    (net (code "124") (name "unconnected-(U6-PadSCK)") (class "Default")
      (node (ref "U6") (pin "SCK") (pinfunction "SCK_SCK") (pintype "unspecified"))
    )
    (net (code "125") (name "unconnected-(U6-PadSCL)") (class "Default")
      (node (ref "U6") (pin "SCL") (pinfunction "SCL_SCL") (pintype "unspecified"))
    )
    (net (code "126") (name "unconnected-(U6-PadSDA)") (class "Default")
      (node (ref "U6") (pin "SDA") (pinfunction "SDA_SDA") (pintype "unspecified"))
    )
    (net (code "127") (name "unconnected-(U6-PadVCC)") (class "Default")
      (node (ref "U6") (pin "VCC") (pinfunction "VCC_VCC") (pintype "unspecified"))
    )
    (net (code "128") (name "unconnected-(U6-PadVIN)") (class "Default")
      (node (ref "U6") (pin "VIN") (pinfunction "VIN_VIN") (pintype "unspecified"))
    )
    (net (code "129") (name "unconnected-(U6-RESET-PadRESET@0)") (class "Default")
      (node (ref "U6") (pin "RESET@0") (pinfunction "RESET_RESET@0") (pintype "unspecified"))
    )
    (net (code "130") (name "unconnected-(U6-RESET-PadRESET@1)") (class "Default")
      (node (ref "U6") (pin "RESET@1") (pinfunction "RESET_RESET@1") (pintype "unspecified"))
    )
    (net (code "131") (name "unconnected-(U15-3V-Pad2)") (class "Default")
      (node (ref "U15") (pin "2") (pinfunction "3V_2") (pintype "unspecified"))
    )
    (net (code "132") (name "unconnected-(U15-CSAG-Pad6)") (class "Default")
      (node (ref "U15") (pin "6") (pinfunction "CSAG_6") (pintype "unspecified"))
    )
    (net (code "133") (name "unconnected-(U15-CSM-Pad7)") (class "Default")
      (node (ref "U15") (pin "7") (pinfunction "CSM_7") (pintype "unspecified"))
    )
    (net (code "134") (name "unconnected-(U15-DEN-Pad10)") (class "Default")
      (node (ref "U15") (pin "10") (pinfunction "DEN_10") (pintype "unspecified"))
    )
    (net (code "135") (name "unconnected-(U15-DOM-Pad9)") (class "Default")
      (node (ref "U15") (pin "9") (pinfunction "DOM_9") (pintype "unspecified"))
    )
    (net (code "136") (name "unconnected-(U15-DRDY-Pad14)") (class "Default")
      (node (ref "U15") (pin "14") (pinfunction "DRDY_14") (pintype "unspecified"))
    )
    (net (code "137") (name "unconnected-(U15-GND-Pad3)") (class "Default")
      (node (ref "U15") (pin "3") (pinfunction "GND_3") (pintype "unspecified"))
    )
    (net (code "138") (name "unconnected-(U15-INT1-Pad12)") (class "Default")
      (node (ref "U15") (pin "12") (pinfunction "INT1_12") (pintype "unspecified"))
    )
    (net (code "139") (name "unconnected-(U15-INT2-Pad11)") (class "Default")
      (node (ref "U15") (pin "11") (pinfunction "INT2_11") (pintype "unspecified"))
    )
    (net (code "140") (name "unconnected-(U15-INTM-Pad13)") (class "Default")
      (node (ref "U15") (pin "13") (pinfunction "INTM_13") (pintype "unspecified"))
    )
    (net (code "141") (name "unconnected-(U15-SDOAG-Pad8)") (class "Default")
      (node (ref "U15") (pin "8") (pinfunction "SDOAG_8") (pintype "unspecified"))
    )
  )
)
